# Board-Front.net
KiCad netlist of a schematic drawn in EAGLE
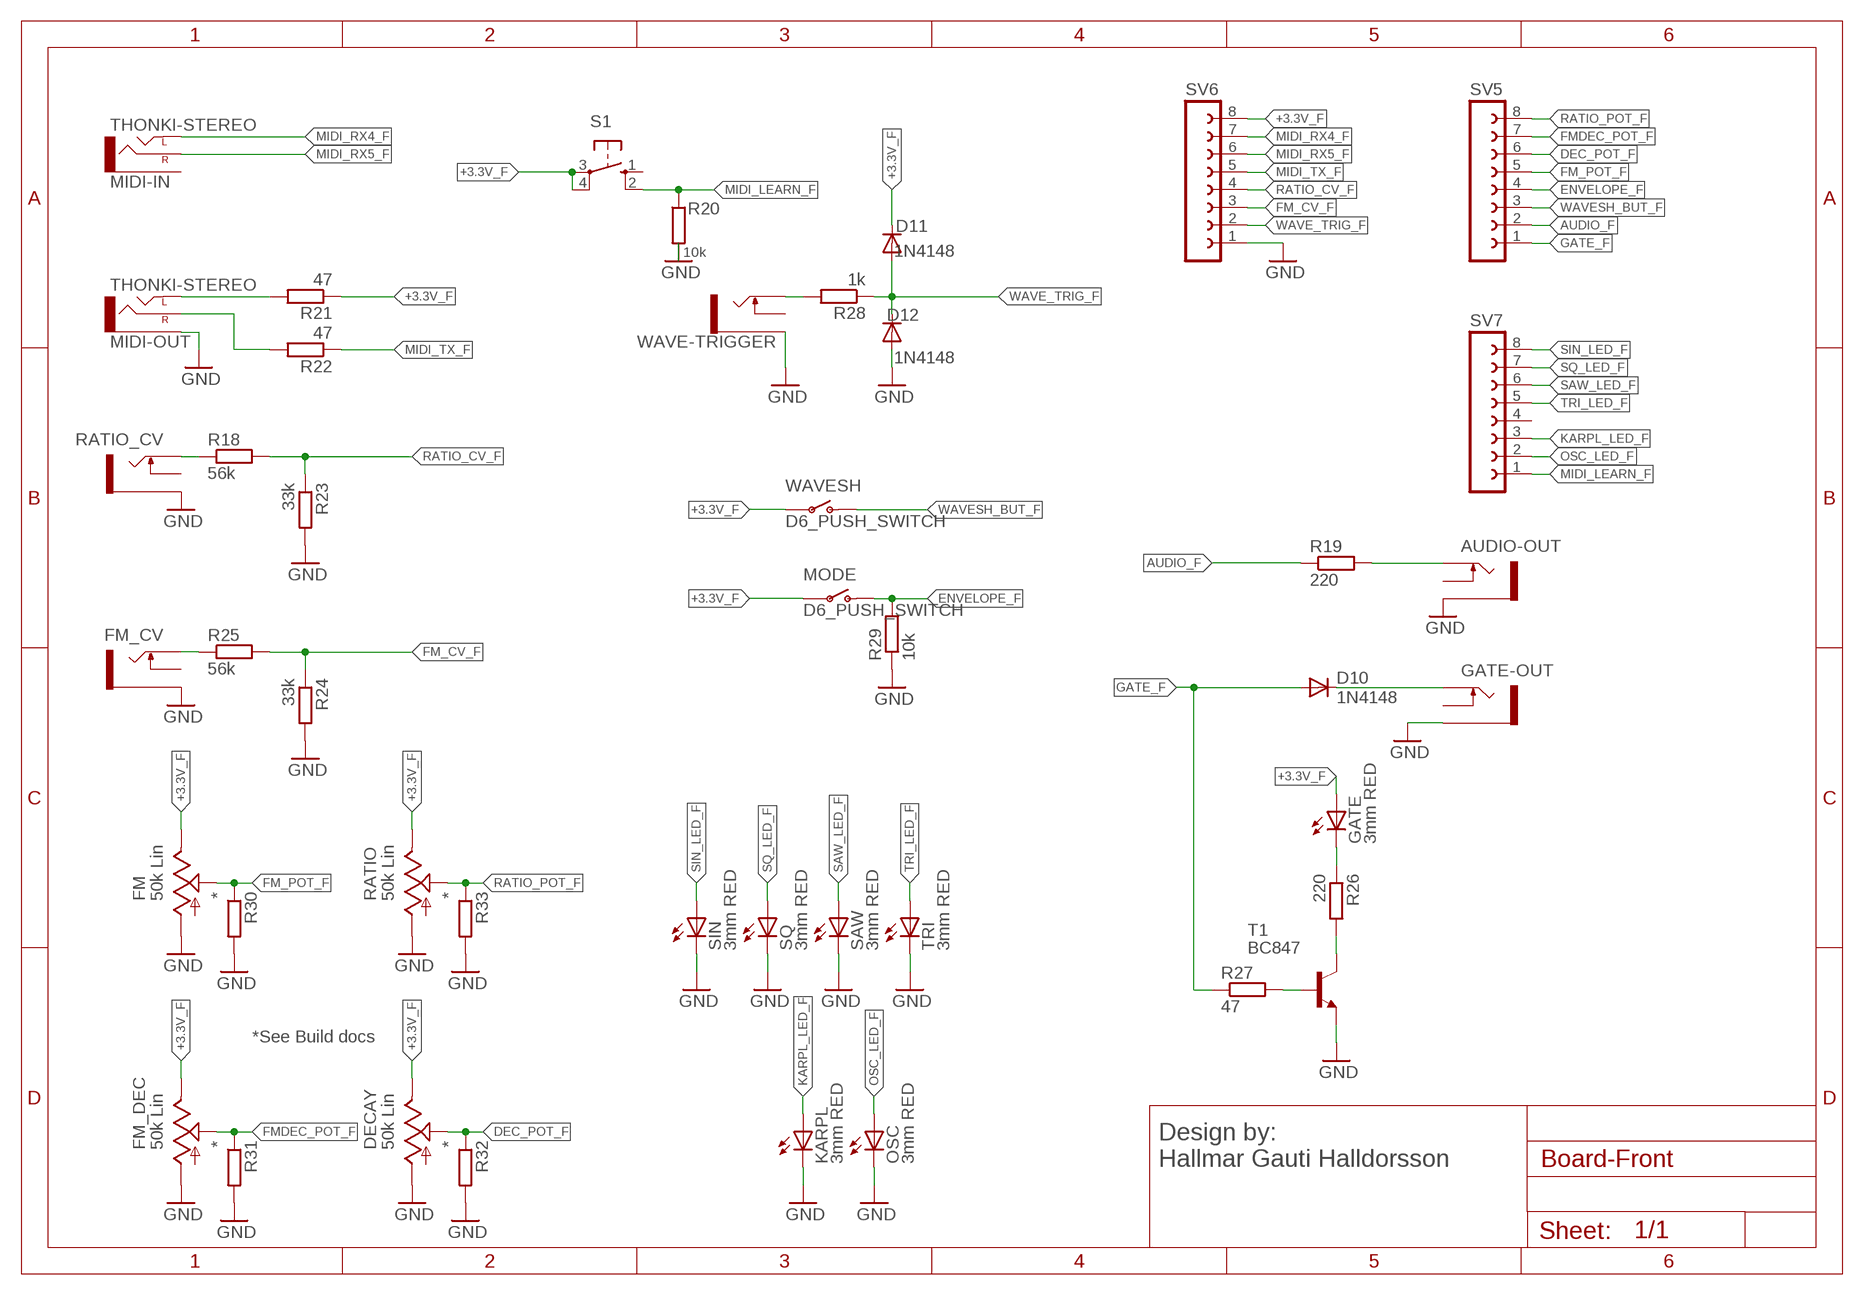
[diagram p0: schematic, sheet 1]

(export (version "E")
  (design (tool "Eeschema 10.0.6"))
  (components
    (comp (ref "AUDIO-OUT")
      (value "THONKICONNNEW")
      (footprint "eagle-import:WQP-PJ301M-12_JACK")
      (libsource (lib "eagle-import") (part "THONKICONNNEW"))
    )
    (comp (ref "D10")
      (value "1N4148")
      (footprint "eagle-import:DO35-7")
      (libsource (lib "eagle-import") (part "1N4148DO35-7"))
    )
    (comp (ref "D11")
      (value "1N4148")
      (footprint "eagle-import:DO35-7")
      (libsource (lib "eagle-import") (part "1N4148DO35-7"))
    )
    (comp (ref "D12")
      (value "1N4148")
      (footprint "eagle-import:DO35-7")
      (libsource (lib "eagle-import") (part "1N4148DO35-7"))
    )
    (comp (ref "DECAY")
      (value "50k Lin")
      (footprint "eagle-import:9MM_SNAP-IN_POT")
      (libsource (lib "eagle-import") (part "9MM_SNAP-IN_POT_"))
    )
    (comp (ref "FM")
      (value "50k Lin")
      (footprint "eagle-import:9MM_SNAP-IN_POT")
      (libsource (lib "eagle-import") (part "9MM_SNAP-IN_POT_"))
    )
    (comp (ref "FM_CV")
      (value "THONKICONNNEW")
      (footprint "eagle-import:WQP-PJ301M-12_JACK")
      (libsource (lib "eagle-import") (part "THONKICONNNEW"))
    )
    (comp (ref "FM_DEC")
      (value "50k Lin")
      (footprint "eagle-import:9MM_SNAP-IN_POT")
      (libsource (lib "eagle-import") (part "9MM_SNAP-IN_POT_"))
    )
    (comp (ref "GATE")
      (value "3mm RED")
      (footprint "eagle-import:LED3MM")
      (libsource (lib "eagle-import") (part "LED3MM"))
    )
    (comp (ref "GATE-OUT")
      (value "THONKICONNNEW")
      (footprint "eagle-import:WQP-PJ301M-12_JACK")
      (libsource (lib "eagle-import") (part "THONKICONNNEW"))
    )
    (comp (ref "KARPL")
      (value "3mm RED")
      (footprint "eagle-import:LED3MM")
      (libsource (lib "eagle-import") (part "LED3MM"))
    )
    (comp (ref "MIDI-IN")
      (value "THONKI-STEREO")
      (footprint "eagle-import:WQP-PJ366ST_JACK")
      (libsource (lib "eagle-import") (part "THONKI-STEREO"))
    )
    (comp (ref "MIDI-OUT")
      (value "THONKI-STEREO")
      (footprint "eagle-import:WQP-PJ366ST_JACK")
      (libsource (lib "eagle-import") (part "THONKI-STEREO"))
    )
    (comp (ref "MODE")
      (value "D6_PUSH_SWITCH")
      (footprint "eagle-import:D6_PUSH_SWITCH")
      (libsource (lib "eagle-import") (part "D6_PUSH_SWITCH"))
    )
    (comp (ref "OSC")
      (value "3mm RED")
      (footprint "eagle-import:LED3MM")
      (libsource (lib "eagle-import") (part "LED3MM"))
    )
    (comp (ref "R18")
      (value "56k")
      (footprint "eagle-import:M1206")
      (libsource (lib "eagle-import") (part "R-EU_M1206"))
    )
    (comp (ref "R19")
      (value "220")
      (footprint "eagle-import:M1206")
      (libsource (lib "eagle-import") (part "R-EU_M1206"))
    )
    (comp (ref "R20")
      (value "10k")
      (footprint "eagle-import:M1206")
      (libsource (lib "eagle-import") (part "R-EU_M1206"))
    )
    (comp (ref "R21")
      (value "47")
      (footprint "eagle-import:M1206")
      (libsource (lib "eagle-import") (part "R-EU_M1206"))
    )
    (comp (ref "R22")
      (value "47")
      (footprint "eagle-import:M1206")
      (libsource (lib "eagle-import") (part "R-EU_M1206"))
    )
    (comp (ref "R23")
      (value "33k")
      (footprint "eagle-import:M1206")
      (libsource (lib "eagle-import") (part "R-EU_M1206"))
    )
    (comp (ref "R24")
      (value "33k")
      (footprint "eagle-import:M1206")
      (libsource (lib "eagle-import") (part "R-EU_M1206"))
    )
    (comp (ref "R25")
      (value "56k")
      (footprint "eagle-import:M1206")
      (libsource (lib "eagle-import") (part "R-EU_M1206"))
    )
    (comp (ref "R26")
      (value "220")
      (footprint "eagle-import:M1206")
      (libsource (lib "eagle-import") (part "R-EU_M1206"))
    )
    (comp (ref "R27")
      (value "47")
      (footprint "eagle-import:M1206")
      (libsource (lib "eagle-import") (part "R-EU_M1206"))
    )
    (comp (ref "R28")
      (value "1k")
      (footprint "eagle-import:M1206")
      (libsource (lib "eagle-import") (part "R-EU_M1206"))
    )
    (comp (ref "R29")
      (value "10k")
      (footprint "eagle-import:M1206")
      (libsource (lib "eagle-import") (part "R-EU_M1206"))
    )
    (comp (ref "R30")
      (value "*")
      (footprint "eagle-import:M1206")
      (libsource (lib "eagle-import") (part "R-EU_M1206"))
    )
    (comp (ref "R31")
      (value "*")
      (footprint "eagle-import:M1206")
      (libsource (lib "eagle-import") (part "R-EU_M1206"))
    )
    (comp (ref "R32")
      (value "*")
      (footprint "eagle-import:M1206")
      (libsource (lib "eagle-import") (part "R-EU_M1206"))
    )
    (comp (ref "R33")
      (value "*")
      (footprint "eagle-import:M1206")
      (libsource (lib "eagle-import") (part "R-EU_M1206"))
    )
    (comp (ref "RATIO")
      (value "50k Lin")
      (footprint "eagle-import:9MM_SNAP-IN_POT")
      (libsource (lib "eagle-import") (part "9MM_SNAP-IN_POT_"))
    )
    (comp (ref "RATIO_CV")
      (value "THONKICONNNEW")
      (footprint "eagle-import:WQP-PJ301M-12_JACK")
      (libsource (lib "eagle-import") (part "THONKICONNNEW"))
    )
    (comp (ref "S1")
      (value "10-XX")
      (footprint "eagle-import:B3F-10XX")
      (fields (field (name "MPN") "B3F-1000"))
      (libsource (lib "eagle-import") (part "10-XX"))
    )
    (comp (ref "SAW")
      (value "3mm RED")
      (footprint "eagle-import:LED3MM")
      (libsource (lib "eagle-import") (part "LED3MM"))
    )
    (comp (ref "SIN")
      (value "3mm RED")
      (footprint "eagle-import:LED3MM")
      (libsource (lib "eagle-import") (part "LED3MM"))
    )
    (comp (ref "SQ")
      (value "3mm RED")
      (footprint "eagle-import:LED3MM")
      (libsource (lib "eagle-import") (part "LED3MM"))
    )
    (comp (ref "SV5")
      (value "FE08-1")
      (footprint "eagle-import:FE08")
      (libsource (lib "eagle-import") (part "FE08-1"))
    )
    (comp (ref "SV6")
      (value "FE08-1")
      (footprint "eagle-import:FE08")
      (libsource (lib "eagle-import") (part "FE08-1"))
    )
    (comp (ref "SV7")
      (value "FE08-1")
      (footprint "eagle-import:FE08")
      (libsource (lib "eagle-import") (part "FE08-1"))
    )
    (comp (ref "T1")
      (value "BC847")
      (footprint "eagle-import:SOT23")
      (libsource (lib "eagle-import") (part "BC847"))
    )
    (comp (ref "TRI")
      (value "3mm RED")
      (footprint "eagle-import:LED3MM")
      (libsource (lib "eagle-import") (part "LED3MM"))
    )
    (comp (ref "WAVE-TRIGGER")
      (value "THONKICONNNEW")
      (footprint "eagle-import:WQP-PJ301M-12_JACK")
      (libsource (lib "eagle-import") (part "THONKICONNNEW"))
    )
    (comp (ref "WAVESH")
      (value "D6_PUSH_SWITCH")
      (footprint "eagle-import:D6_PUSH_SWITCH")
      (libsource (lib "eagle-import") (part "D6_PUSH_SWITCH"))
    )
  )
  (nets
    (net (code "1") (name "+3.3V_F") (class "Default")
      (node (ref "D11") (pin "C") (pinfunction "C_C") (pintype "passive"))
      (node (ref "DECAY") (pin "3") (pinfunction "E_3") (pintype "passive"))
      (node (ref "FM") (pin "3") (pinfunction "E_3") (pintype "passive"))
      (node (ref "FM_DEC") (pin "3") (pinfunction "E_3") (pintype "passive"))
      (node (ref "GATE") (pin "A") (pinfunction "A_A") (pintype "passive"))
      (node (ref "MODE") (pin "P$3") (pinfunction "P_P$3") (pintype "passive"))
      (node (ref "MODE") (pin "P$4") (pinfunction "P_P$4") (pintype "passive"))
      (node (ref "R21") (pin "1") (pinfunction "1_1") (pintype "passive"))
      (node (ref "RATIO") (pin "3") (pinfunction "E_3") (pintype "passive"))
      (node (ref "S1") (pin "3") (pinfunction "P_3") (pintype "passive"))
      (node (ref "S1") (pin "4") (pinfunction "P1_4") (pintype "passive"))
      (node (ref "SV6") (pin "8") (pinfunction "8_8") (pintype "passive"))
      (node (ref "WAVESH") (pin "P$3") (pinfunction "P_P$3") (pintype "passive"))
      (node (ref "WAVESH") (pin "P$4") (pinfunction "P_P$4") (pintype "passive"))
    )
    (net (code "2") (name "AUDIO_F") (class "Default")
      (node (ref "R19") (pin "1") (pinfunction "1_1") (pintype "passive"))
      (node (ref "SV5") (pin "2") (pinfunction "2_2") (pintype "passive"))
    )
    (net (code "3") (name "DEC_POT_F") (class "Default")
      (node (ref "DECAY") (pin "2") (pinfunction "S_2") (pintype "passive"))
      (node (ref "R32") (pin "1") (pinfunction "1_1") (pintype "passive"))
      (node (ref "SV5") (pin "6") (pinfunction "6_6") (pintype "passive"))
    )
    (net (code "4") (name "ENVELOPE_F") (class "Default")
      (node (ref "MODE") (pin "P$1") (pinfunction "O_P$1") (pintype "passive"))
      (node (ref "MODE") (pin "P$2") (pinfunction "O_P$2") (pintype "passive"))
      (node (ref "R29") (pin "2") (pinfunction "2_2") (pintype "passive"))
      (node (ref "SV5") (pin "4") (pinfunction "4_4") (pintype "passive"))
    )
    (net (code "5") (name "FMDEC_POT_F") (class "Default")
      (node (ref "FM_DEC") (pin "2") (pinfunction "S_2") (pintype "passive"))
      (node (ref "R31") (pin "1") (pinfunction "1_1") (pintype "passive"))
      (node (ref "SV5") (pin "7") (pinfunction "7_7") (pintype "passive"))
    )
    (net (code "6") (name "FM_CV_F") (class "Default")
      (node (ref "R24") (pin "1") (pinfunction "1_1") (pintype "passive"))
      (node (ref "R25") (pin "2") (pinfunction "2_2") (pintype "passive"))
      (node (ref "SV6") (pin "3") (pinfunction "3_3") (pintype "passive"))
    )
    (net (code "7") (name "FM_POT_F") (class "Default")
      (node (ref "FM") (pin "2") (pinfunction "S_2") (pintype "passive"))
      (node (ref "R30") (pin "1") (pinfunction "1_1") (pintype "passive"))
      (node (ref "SV5") (pin "5") (pinfunction "5_5") (pintype "passive"))
    )
    (net (code "8") (name "GATE_F") (class "Default")
      (node (ref "D10") (pin "A") (pinfunction "A_A") (pintype "passive"))
      (node (ref "R27") (pin "1") (pinfunction "1_1") (pintype "passive"))
      (node (ref "SV5") (pin "1") (pinfunction "1_1") (pintype "passive"))
    )
    (net (code "9") (name "GND") (class "Default")
      (node (ref "AUDIO-OUT") (pin "P$3_SLEEVE") (pinfunction "SLEEVE_P$3_SLEEVE") (pintype "passive"))
      (node (ref "D12") (pin "A") (pinfunction "A_A") (pintype "passive"))
      (node (ref "DECAY") (pin "1") (pinfunction "A_1") (pintype "passive"))
      (node (ref "FM") (pin "1") (pinfunction "A_1") (pintype "passive"))
      (node (ref "FM_CV") (pin "P$3_SLEEVE") (pinfunction "SLEEVE_P$3_SLEEVE") (pintype "passive"))
      (node (ref "FM_DEC") (pin "1") (pinfunction "A_1") (pintype "passive"))
      (node (ref "GATE-OUT") (pin "P$3_SLEEVE") (pinfunction "SLEEVE_P$3_SLEEVE") (pintype "passive"))
      (node (ref "KARPL") (pin "K") (pinfunction "C_K") (pintype "passive"))
      (node (ref "MIDI-OUT") (pin "P$3_SLEEVE") (pinfunction "SLEEVE_P$3_SLEEVE") (pintype "bidirectional"))
      (node (ref "OSC") (pin "K") (pinfunction "C_K") (pintype "passive"))
      (node (ref "R20") (pin "2") (pinfunction "2_2") (pintype "passive"))
      (node (ref "R23") (pin "2") (pinfunction "2_2") (pintype "passive"))
      (node (ref "R24") (pin "2") (pinfunction "2_2") (pintype "passive"))
      (node (ref "R29") (pin "1") (pinfunction "1_1") (pintype "passive"))
      (node (ref "R30") (pin "2") (pinfunction "2_2") (pintype "passive"))
      (node (ref "R31") (pin "2") (pinfunction "2_2") (pintype "passive"))
      (node (ref "R32") (pin "2") (pinfunction "2_2") (pintype "passive"))
      (node (ref "R33") (pin "2") (pinfunction "2_2") (pintype "passive"))
      (node (ref "RATIO") (pin "1") (pinfunction "A_1") (pintype "passive"))
      (node (ref "RATIO_CV") (pin "P$3_SLEEVE") (pinfunction "SLEEVE_P$3_SLEEVE") (pintype "passive"))
      (node (ref "SAW") (pin "K") (pinfunction "C_K") (pintype "passive"))
      (node (ref "SIN") (pin "K") (pinfunction "C_K") (pintype "passive"))
      (node (ref "SQ") (pin "K") (pinfunction "C_K") (pintype "passive"))
      (node (ref "SV6") (pin "1") (pinfunction "1_1") (pintype "passive"))
      (node (ref "T1") (pin "2") (pinfunction "E_2") (pintype "passive"))
      (node (ref "TRI") (pin "K") (pinfunction "C_K") (pintype "passive"))
      (node (ref "WAVE-TRIGGER") (pin "P$3_SLEEVE") (pinfunction "SLEEVE_P$3_SLEEVE") (pintype "passive"))
    )
    (net (code "10") (name "KARPL_LED_F") (class "Default")
      (node (ref "KARPL") (pin "A") (pinfunction "A_A") (pintype "passive"))
      (node (ref "SV7") (pin "3") (pinfunction "3_3") (pintype "passive"))
    )
    (net (code "11") (name "MIDI_LEARN_F") (class "Default")
      (node (ref "R20") (pin "1") (pinfunction "1_1") (pintype "passive"))
      (node (ref "S1") (pin "2") (pinfunction "S1_2") (pintype "passive"))
      (node (ref "SV7") (pin "1") (pinfunction "1_1") (pintype "passive"))
    )
    (net (code "12") (name "MIDI_RX4_F") (class "Default")
      (node (ref "MIDI-IN") (pin "P$1_TIP") (pinfunction "LEFT_P$1_TIP") (pintype "bidirectional"))
      (node (ref "SV6") (pin "7") (pinfunction "7_7") (pintype "passive"))
    )
    (net (code "13") (name "MIDI_RX5_F") (class "Default")
      (node (ref "MIDI-IN") (pin "P$2_SWITCH") (pinfunction "RIGHT_P$2_SWITCH") (pintype "bidirectional"))
      (node (ref "SV6") (pin "6") (pinfunction "6_6") (pintype "passive"))
    )
    (net (code "14") (name "MIDI_TX_F") (class "Default")
      (node (ref "R22") (pin "1") (pinfunction "1_1") (pintype "passive"))
      (node (ref "SV6") (pin "5") (pinfunction "5_5") (pintype "passive"))
    )
    (net (code "15") (name "Net-(AUDIO-OUT-TIP)") (class "Default")
      (node (ref "AUDIO-OUT") (pin "P$1_TIP") (pinfunction "TIP_P$1_TIP") (pintype "passive"))
      (node (ref "R19") (pin "2") (pinfunction "2_2") (pintype "passive"))
    )
    (net (code "16") (name "Net-(FM_CV-TIP)") (class "Default")
      (node (ref "FM_CV") (pin "P$1_TIP") (pinfunction "TIP_P$1_TIP") (pintype "passive"))
      (node (ref "R25") (pin "1") (pinfunction "1_1") (pintype "passive"))
    )
    (net (code "17") (name "Net-(GATE-C)") (class "Default")
      (node (ref "GATE") (pin "K") (pinfunction "C_K") (pintype "passive"))
      (node (ref "R26") (pin "1") (pinfunction "1_1") (pintype "passive"))
    )
    (net (code "18") (name "Net-(GATE-OUT-TIP)") (class "Default")
      (node (ref "D10") (pin "C") (pinfunction "C_C") (pintype "passive"))
      (node (ref "GATE-OUT") (pin "P$1_TIP") (pinfunction "TIP_P$1_TIP") (pintype "passive"))
    )
    (net (code "19") (name "Net-(MIDI-OUT-LEFT)") (class "Default")
      (node (ref "MIDI-OUT") (pin "P$1_TIP") (pinfunction "LEFT_P$1_TIP") (pintype "bidirectional"))
      (node (ref "R21") (pin "2") (pinfunction "2_2") (pintype "passive"))
    )
    (net (code "20") (name "Net-(MIDI-OUT-RIGHT)") (class "Default")
      (node (ref "MIDI-OUT") (pin "P$2_SWITCH") (pinfunction "RIGHT_P$2_SWITCH") (pintype "bidirectional"))
      (node (ref "R22") (pin "2") (pinfunction "2_2") (pintype "passive"))
    )
    (net (code "21") (name "Net-(RATIO_CV-TIP)") (class "Default")
      (node (ref "R18") (pin "1") (pinfunction "1_1") (pintype "passive"))
      (node (ref "RATIO_CV") (pin "P$1_TIP") (pinfunction "TIP_P$1_TIP") (pintype "passive"))
    )
    (net (code "22") (name "Net-(T1-B)") (class "Default")
      (node (ref "R27") (pin "2") (pinfunction "2_2") (pintype "passive"))
      (node (ref "T1") (pin "1") (pinfunction "B_1") (pintype "passive"))
    )
    (net (code "23") (name "Net-(T1-C)") (class "Default")
      (node (ref "R26") (pin "2") (pinfunction "2_2") (pintype "passive"))
      (node (ref "T1") (pin "3") (pinfunction "C_3") (pintype "passive"))
    )
    (net (code "24") (name "Net-(WAVE-TRIGGER-TIP)") (class "Default")
      (node (ref "R28") (pin "2") (pinfunction "2_2") (pintype "passive"))
      (node (ref "WAVE-TRIGGER") (pin "P$1_TIP") (pinfunction "TIP_P$1_TIP") (pintype "passive"))
    )
    (net (code "25") (name "OSC_LED_F") (class "Default")
      (node (ref "OSC") (pin "A") (pinfunction "A_A") (pintype "passive"))
      (node (ref "SV7") (pin "2") (pinfunction "2_2") (pintype "passive"))
    )
    (net (code "26") (name "RATIO_CV_F") (class "Default")
      (node (ref "R18") (pin "2") (pinfunction "2_2") (pintype "passive"))
      (node (ref "R23") (pin "1") (pinfunction "1_1") (pintype "passive"))
      (node (ref "SV6") (pin "4") (pinfunction "4_4") (pintype "passive"))
    )
    (net (code "27") (name "RATIO_POT_F") (class "Default")
      (node (ref "R33") (pin "1") (pinfunction "1_1") (pintype "passive"))
      (node (ref "RATIO") (pin "2") (pinfunction "S_2") (pintype "passive"))
      (node (ref "SV5") (pin "8") (pinfunction "8_8") (pintype "passive"))
    )
    (net (code "28") (name "SAW_LED_F") (class "Default")
      (node (ref "SAW") (pin "A") (pinfunction "A_A") (pintype "passive"))
      (node (ref "SV7") (pin "6") (pinfunction "6_6") (pintype "passive"))
    )
    (net (code "29") (name "SIN_LED_F") (class "Default")
      (node (ref "SIN") (pin "A") (pinfunction "A_A") (pintype "passive"))
      (node (ref "SV7") (pin "8") (pinfunction "8_8") (pintype "passive"))
    )
    (net (code "30") (name "SQ_LED_F") (class "Default")
      (node (ref "SQ") (pin "A") (pinfunction "A_A") (pintype "passive"))
      (node (ref "SV7") (pin "7") (pinfunction "7_7") (pintype "passive"))
    )
    (net (code "31") (name "TRI_LED_F") (class "Default")
      (node (ref "SV7") (pin "5") (pinfunction "5_5") (pintype "passive"))
      (node (ref "TRI") (pin "A") (pinfunction "A_A") (pintype "passive"))
    )
    (net (code "32") (name "WAVESH_BUT_F") (class "Default")
      (node (ref "SV5") (pin "3") (pinfunction "3_3") (pintype "passive"))
      (node (ref "WAVESH") (pin "P$1") (pinfunction "O_P$1") (pintype "passive"))
      (node (ref "WAVESH") (pin "P$2") (pinfunction "O_P$2") (pintype "passive"))
    )
    (net (code "33") (name "WAVE_TRIG_F") (class "Default")
      (node (ref "D11") (pin "A") (pinfunction "A_A") (pintype "passive"))
      (node (ref "D12") (pin "C") (pinfunction "C_C") (pintype "passive"))
      (node (ref "R28") (pin "1") (pinfunction "1_1") (pintype "passive"))
      (node (ref "SV6") (pin "2") (pinfunction "2_2") (pintype "passive"))
    )
    (net (code "34") (name "unconnected-(AUDIO-OUT-SWITCH-PadP$2_SWITCH)") (class "Default")
      (node (ref "AUDIO-OUT") (pin "P$2_SWITCH") (pinfunction "SWITCH_P$2_SWITCH") (pintype "passive"))
    )
    (net (code "35") (name "unconnected-(FM_CV-SWITCH-PadP$2_SWITCH)") (class "Default")
      (node (ref "FM_CV") (pin "P$2_SWITCH") (pinfunction "SWITCH_P$2_SWITCH") (pintype "passive"))
    )
    (net (code "36") (name "unconnected-(GATE-OUT-SWITCH-PadP$2_SWITCH)") (class "Default")
      (node (ref "GATE-OUT") (pin "P$2_SWITCH") (pinfunction "SWITCH_P$2_SWITCH") (pintype "passive"))
    )
    (net (code "37") (name "unconnected-(MIDI-IN-SLEEVE-PadP$3_SLEEVE)") (class "Default")
      (node (ref "MIDI-IN") (pin "P$3_SLEEVE") (pinfunction "SLEEVE_P$3_SLEEVE") (pintype "bidirectional"))
    )
    (net (code "38") (name "unconnected-(RATIO_CV-SWITCH-PadP$2_SWITCH)") (class "Default")
      (node (ref "RATIO_CV") (pin "P$2_SWITCH") (pinfunction "SWITCH_P$2_SWITCH") (pintype "passive"))
    )
    (net (code "39") (name "unconnected-(S1-S-Pad1)") (class "Default")
      (node (ref "S1") (pin "1") (pinfunction "S_1") (pintype "passive"))
    )
    (net (code "40") (name "unconnected-(SV7-Pad4)") (class "Default")
      (node (ref "SV7") (pin "4") (pinfunction "4_4") (pintype "passive"))
    )
    (net (code "41") (name "unconnected-(WAVE-TRIGGER-SWITCH-PadP$2_SWITCH)") (class "Default")
      (node (ref "WAVE-TRIGGER") (pin "P$2_SWITCH") (pinfunction "SWITCH_P$2_SWITCH") (pintype "passive"))
    )
  )
)
